# Nano_only.net
KiCad netlist of a schematic drawn in EAGLE
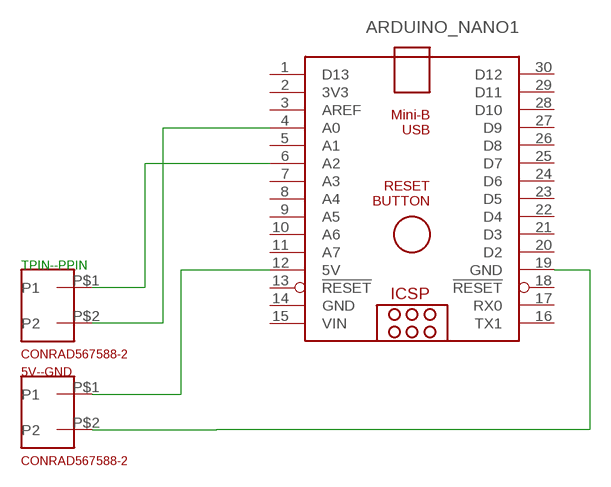
[diagram p0: schematic, sheet 1]

(export (version "E")
  (design (tool "Eeschema 10.0.6"))
  (components
    (comp (ref "5V--GND")
      (value "CONRAD567588-2")
      (footprint "eagle-import:CONRAD567588")
      (libsource (lib "eagle-import") (part "CONRAD567588-2"))
    )
    (comp (ref "ARDUINO_NANO1")
      (value "ARDUINO_NANO")
      (footprint "eagle-import:ARDUINO_NANO")
      (libsource (lib "eagle-import") (part "ARDUINO_NANO"))
    )
    (comp (ref "TPIN--PPIN")
      (value "CONRAD567588-2")
      (footprint "eagle-import:CONRAD567588")
      (libsource (lib "eagle-import") (part "CONRAD567588-2"))
    )
  )
  (nets
    (net (code "1") (name "/GND") (class "Default")
      (node (ref "ARDUINO_NANO1") (pin "14") (pinfunction "GND_14") (pintype "power_in"))
    )
    (net (code "2") (name "/VIN") (class "Default")
      (node (ref "ARDUINO_NANO1") (pin "15") (pinfunction "VIN_15") (pintype "power_in"))
    )
    (net (code "3") (name "Net-(5V--GND-P1)") (class "Default")
      (node (ref "5V--GND") (pin "P$1") (pinfunction "P1_P$1") (pintype "bidirectional"))
      (node (ref "ARDUINO_NANO1") (pin "12") (pinfunction "5V_12") (pintype "power_in"))
    )
    (net (code "4") (name "Net-(5V--GND-P2)") (class "Default")
      (node (ref "5V--GND") (pin "P$2") (pinfunction "P2_P$2") (pintype "bidirectional"))
      (node (ref "ARDUINO_NANO1") (pin "19") (pinfunction "GND_19") (pintype "power_in"))
    )
    (net (code "5") (name "Net-(ARDUINO_NANO1-A0)") (class "Default")
      (node (ref "ARDUINO_NANO1") (pin "4") (pinfunction "A0_4") (pintype "bidirectional"))
      (node (ref "TPIN--PPIN") (pin "P$2") (pinfunction "P2_P$2") (pintype "bidirectional"))
    )
    (net (code "6") (name "Net-(ARDUINO_NANO1-A2)") (class "Default")
      (node (ref "ARDUINO_NANO1") (pin "6") (pinfunction "A2_6") (pintype "bidirectional"))
      (node (ref "TPIN--PPIN") (pin "P$1") (pinfunction "P1_P$1") (pintype "bidirectional"))
    )
    (net (code "7") (name "unconnected-(ARDUINO_NANO1-3V3-Pad2)") (class "Default")
      (node (ref "ARDUINO_NANO1") (pin "2") (pinfunction "3V3_2") (pintype "output"))
    )
    (net (code "8") (name "unconnected-(ARDUINO_NANO1-A1-Pad5)") (class "Default")
      (node (ref "ARDUINO_NANO1") (pin "5") (pinfunction "A1_5") (pintype "bidirectional"))
    )
    (net (code "9") (name "unconnected-(ARDUINO_NANO1-A3-Pad7)") (class "Default")
      (node (ref "ARDUINO_NANO1") (pin "7") (pinfunction "A3_7") (pintype "bidirectional"))
    )
    (net (code "10") (name "unconnected-(ARDUINO_NANO1-A4-Pad8)") (class "Default")
      (node (ref "ARDUINO_NANO1") (pin "8") (pinfunction "A4_8") (pintype "bidirectional"))
    )
    (net (code "11") (name "unconnected-(ARDUINO_NANO1-A5-Pad9)") (class "Default")
      (node (ref "ARDUINO_NANO1") (pin "9") (pinfunction "A5_9") (pintype "bidirectional"))
    )
    (net (code "12") (name "unconnected-(ARDUINO_NANO1-A6-Pad10)") (class "Default")
      (node (ref "ARDUINO_NANO1") (pin "10") (pinfunction "A6_10") (pintype "bidirectional"))
    )
    (net (code "13") (name "unconnected-(ARDUINO_NANO1-A7-Pad11)") (class "Default")
      (node (ref "ARDUINO_NANO1") (pin "11") (pinfunction "A7_11") (pintype "bidirectional"))
    )
    (net (code "14") (name "unconnected-(ARDUINO_NANO1-AREF-Pad3)") (class "Default")
      (node (ref "ARDUINO_NANO1") (pin "3") (pinfunction "AREF_3") (pintype "input"))
    )
    (net (code "15") (name "unconnected-(ARDUINO_NANO1-D2-Pad20)") (class "Default")
      (node (ref "ARDUINO_NANO1") (pin "20") (pinfunction "D2_20") (pintype "bidirectional"))
    )
    (net (code "16") (name "unconnected-(ARDUINO_NANO1-D3-Pad21)") (class "Default")
      (node (ref "ARDUINO_NANO1") (pin "21") (pinfunction "D3_21") (pintype "bidirectional"))
    )
    (net (code "17") (name "unconnected-(ARDUINO_NANO1-D4-Pad22)") (class "Default")
      (node (ref "ARDUINO_NANO1") (pin "22") (pinfunction "D4_22") (pintype "bidirectional"))
    )
    (net (code "18") (name "unconnected-(ARDUINO_NANO1-D5-Pad23)") (class "Default")
      (node (ref "ARDUINO_NANO1") (pin "23") (pinfunction "D5_23") (pintype "bidirectional"))
    )
    (net (code "19") (name "unconnected-(ARDUINO_NANO1-D6-Pad24)") (class "Default")
      (node (ref "ARDUINO_NANO1") (pin "24") (pinfunction "D6_24") (pintype "bidirectional"))
    )
    (net (code "20") (name "unconnected-(ARDUINO_NANO1-D7-Pad25)") (class "Default")
      (node (ref "ARDUINO_NANO1") (pin "25") (pinfunction "D7_25") (pintype "bidirectional"))
    )
    (net (code "21") (name "unconnected-(ARDUINO_NANO1-D8-Pad26)") (class "Default")
      (node (ref "ARDUINO_NANO1") (pin "26") (pinfunction "D8_26") (pintype "bidirectional"))
    )
    (net (code "22") (name "unconnected-(ARDUINO_NANO1-D9-Pad27)") (class "Default")
      (node (ref "ARDUINO_NANO1") (pin "27") (pinfunction "D9_27") (pintype "bidirectional"))
    )
    (net (code "23") (name "unconnected-(ARDUINO_NANO1-D10-Pad28)") (class "Default")
      (node (ref "ARDUINO_NANO1") (pin "28") (pinfunction "D10_28") (pintype "bidirectional"))
    )
    (net (code "24") (name "unconnected-(ARDUINO_NANO1-D11-Pad29)") (class "Default")
      (node (ref "ARDUINO_NANO1") (pin "29") (pinfunction "D11_29") (pintype "bidirectional"))
    )
    (net (code "25") (name "unconnected-(ARDUINO_NANO1-D12-Pad30)") (class "Default")
      (node (ref "ARDUINO_NANO1") (pin "30") (pinfunction "D12_30") (pintype "bidirectional"))
    )
    (net (code "26") (name "unconnected-(ARDUINO_NANO1-D13-Pad1)") (class "Default")
      (node (ref "ARDUINO_NANO1") (pin "1") (pinfunction "D13_1") (pintype "bidirectional"))
    )
    (net (code "27") (name "unconnected-(ARDUINO_NANO1-RX0-Pad17)") (class "Default")
      (node (ref "ARDUINO_NANO1") (pin "17") (pinfunction "RX0_17") (pintype "bidirectional"))
    )
    (net (code "28") (name "unconnected-(ARDUINO_NANO1-TX1-Pad16)") (class "Default")
      (node (ref "ARDUINO_NANO1") (pin "16") (pinfunction "TX1_16") (pintype "bidirectional"))
    )
    (net (code "29") (name "unconnected-(ARDUINO_NANO1-~{RESET}-Pad13)") (class "Default")
      (node (ref "ARDUINO_NANO1") (pin "13") (pinfunction "~{RESET}_13") (pintype "input"))
    )
    (net (code "30") (name "unconnected-(ARDUINO_NANO1-~{RESET}-Pad18)") (class "Default")
      (node (ref "ARDUINO_NANO1") (pin "18") (pinfunction "~{RESET}_18") (pintype "input"))
    )
  )
)
